# Power_SwitchRegulators.net
KiCad netlist of a schematic drawn in Altium Designer
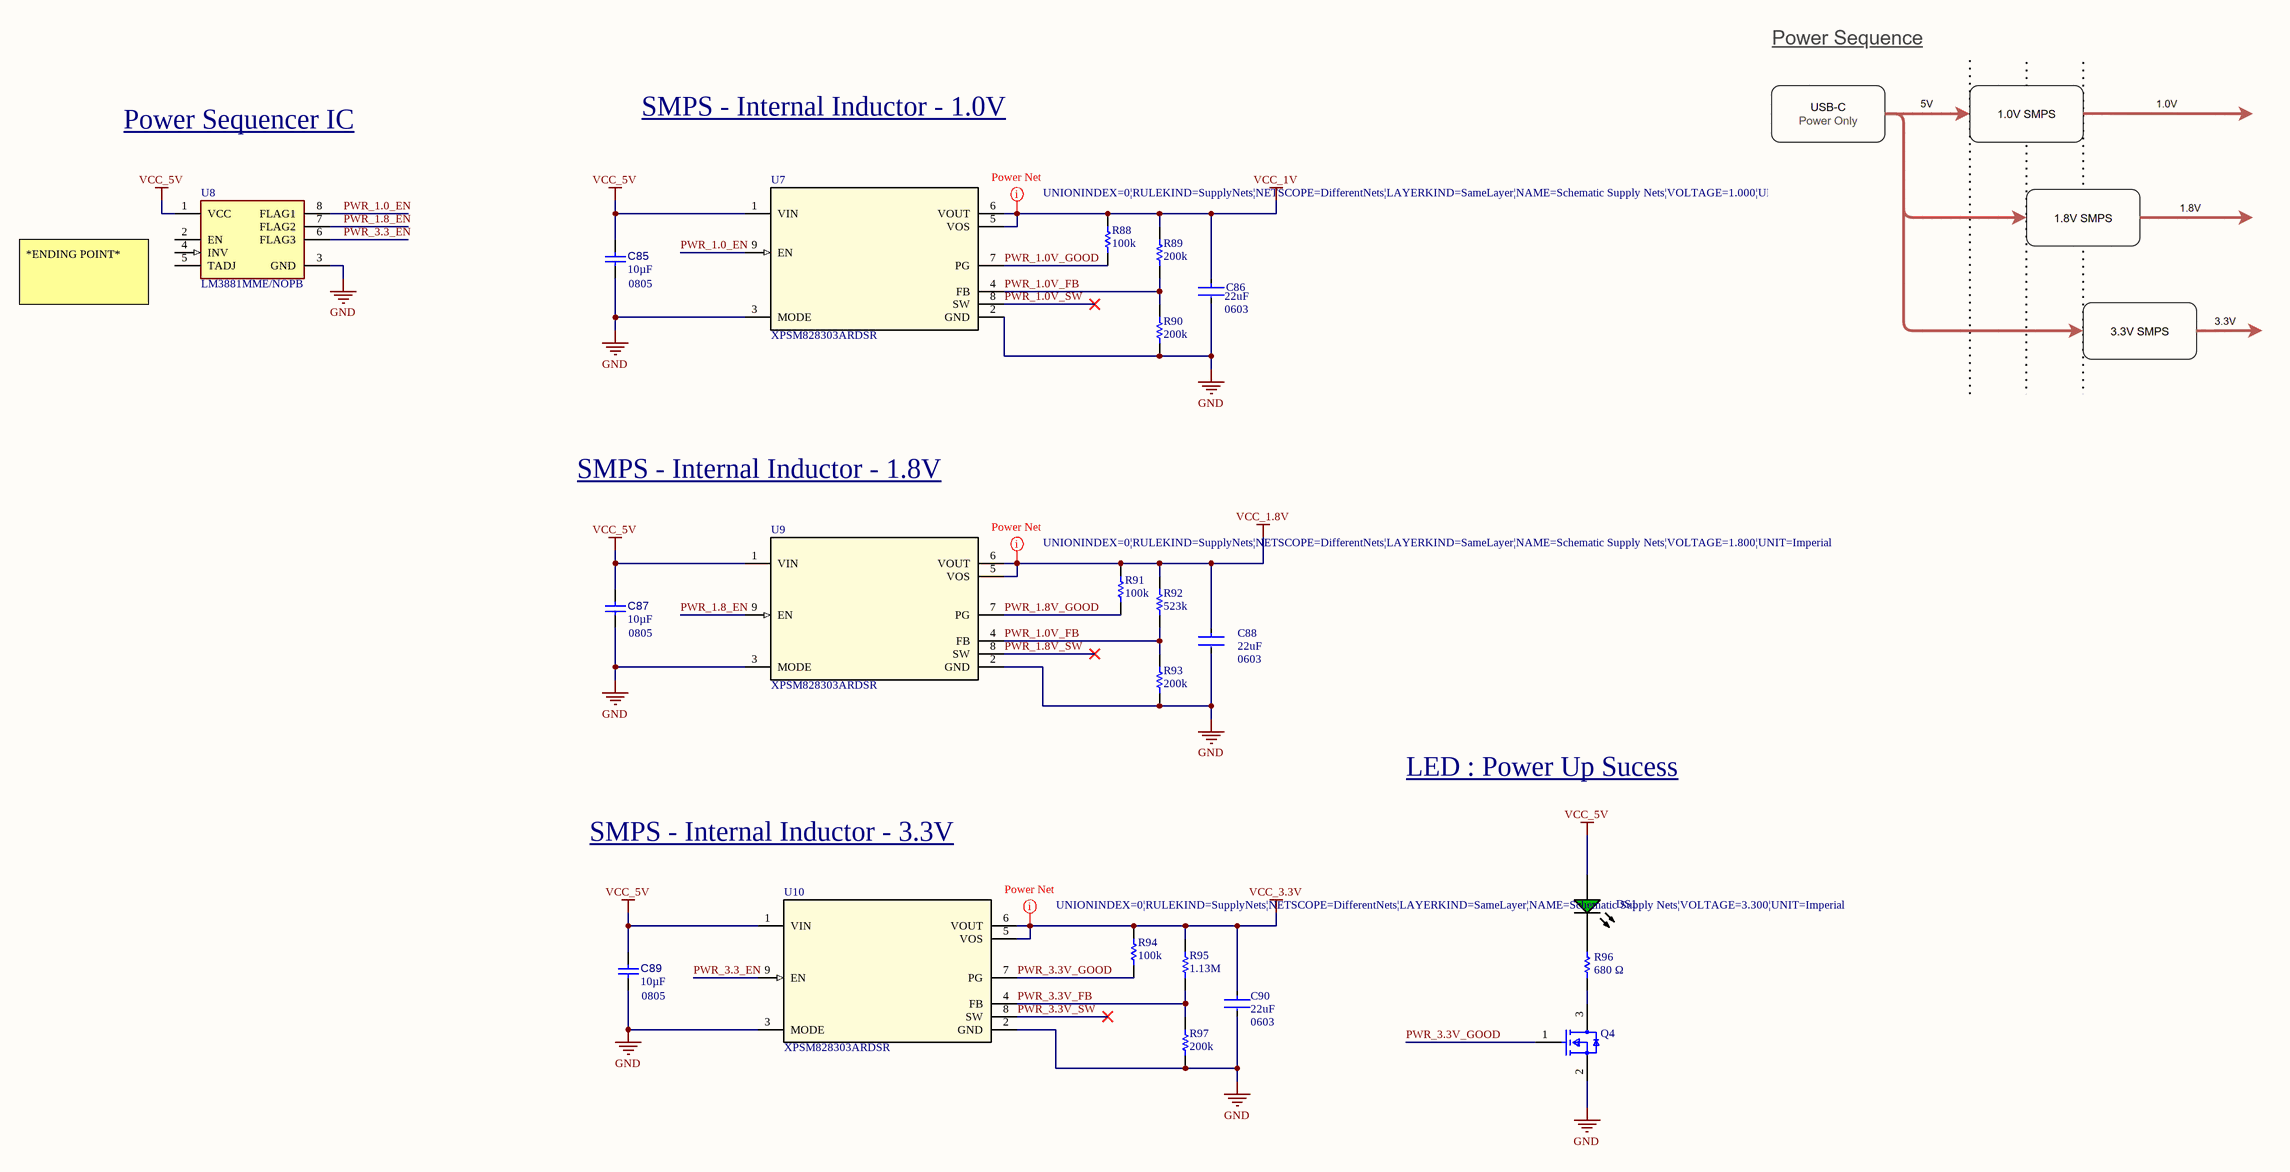
[diagram p0: Power_SwitchRegulators.SchDoc]

(export (version "E")
  (design (tool "Eeschema 10.0.6"))
  (components
    (comp (ref "C85")
      (value "10µF")
      (footprint "CAPC0805(2012)145_L")
      (description "Chip Capacitor, 10µF +/-20%, 25V, 0805, Thickness 1.45 mm")
      (fields
        (field (name "TOLERANCE") "10%")
        (field (name "CASE/PACKAGE") "0805")
        (field (name "Comment") "Capacitor 10µF +/-20% 25V 0805")
      )
      (libsource (lib "Personal Workspace") (part "CAP-NP-2"))
    )
    (comp (ref "C86")
      (value "GRM188R60J226MEA0J")
      (footprint "FP-GRM188-0_2-IPC_C")
      (description "Chip Multilayer Ceramic Capacitors for General Purpose, 0603, 22uF, X5R, 15%, 20%, 6.3V")
      (fields
        (field (name "CAPACITANCE") "22uF")
        (field (name "TOLERANCE") "20%")
        (field (name "CASE/PACKAGE") "0603")
      )
      (libsource (lib "Altium Content Vault") (part "11868f565c42a9108669ba33697ecf6"))
    )
    (comp (ref "C87")
      (value "10µF")
      (footprint "CAPC0805(2012)145_L")
      (description "Chip Capacitor, 10µF +/-20%, 25V, 0805, Thickness 1.45 mm")
      (fields
        (field (name "TOLERANCE") "10%")
        (field (name "CASE/PACKAGE") "0805")
        (field (name "Comment") "Capacitor 10µF +/-20% 25V 0805")
      )
      (libsource (lib "Personal Workspace") (part "CAP-NP-2"))
    )
    (comp (ref "C88")
      (value "GRM188R60J226MEA0J")
      (footprint "FP-GRM188-0_2-IPC_C")
      (description "Chip Multilayer Ceramic Capacitors for General Purpose, 0603, 22uF, X5R, 15%, 20%, 6.3V")
      (fields
        (field (name "CAPACITANCE") "22uF")
        (field (name "TOLERANCE") "20%")
        (field (name "CASE/PACKAGE") "0603")
      )
      (libsource (lib "Altium Content Vault") (part "11868f565c42a9108669ba33697ecf6"))
    )
    (comp (ref "C89")
      (value "10µF")
      (footprint "CAPC0805(2012)145_L")
      (description "Chip Capacitor, 10µF +/-20%, 25V, 0805, Thickness 1.45 mm")
      (fields
        (field (name "TOLERANCE") "10%")
        (field (name "CASE/PACKAGE") "0805")
        (field (name "Comment") "Capacitor 10µF +/-20% 25V 0805")
      )
      (libsource (lib "Personal Workspace") (part "CAP-NP-2"))
    )
    (comp (ref "C90")
      (value "GRM188R60J226MEA0J")
      (footprint "FP-GRM188-0_2-IPC_C")
      (description "Chip Multilayer Ceramic Capacitors for General Purpose, 0603, 22uF, X5R, 15%, 20%, 6.3V")
      (fields
        (field (name "CAPACITANCE") "22uF")
        (field (name "TOLERANCE") "20%")
        (field (name "CASE/PACKAGE") "0603")
      )
      (libsource (lib "Altium Content Vault") (part "11868f565c42a9108669ba33697ecf6"))
    )
    (comp (ref "DS1")
      (value "HSMG-C170")
      (footprint "AVAG-HSMX-C170_V")
      (description "Chip LED, Green, 2.2 V, -40 to 85 degC, 2-Pin SMD, Pb-Free, Tape and Reel")
      (fields (field (name "MANUFACTURER") "Avago"))
      (libsource (lib "Altium Content Vault") (part "LED_GREEN_A1K2-2"))
    )
    (comp (ref "Q4")
      (value "BSS138")
      (footprint "FP-318-08-IPC_B")
      (description "MOSFET N-CH 50V 220MA SOT-23")
      (libsource (lib "Altium Content Vault") (part "3b9c635fedb024a5347a57b145af9cc"))
    )
    (comp (ref "R88")
      (value "100k")
      (footprint "RESC1005X40X25ML05T05")
      (description "Chip Resistor, 100 KOhm, +/- 1%, 0.063 W, -55 to 155 degC, 0402 (1005 Metric)")
      (fields (field (name "POWER") "63mW") (field (name "TOLERANCE") "1%"))
      (libsource (lib "Personal Workspace") (part "RES-2"))
    )
    (comp (ref "R89")
      (value "200k")
      (footprint "RESC0402(1005)_L")
      (description "Chip Resistor, 200 kOhms, +/-1 %, 63 mW, -55 to 155 degC, 0402")
      (fields (field (name "TOLERANCE") "1%") (field (name "POWER") "63mW"))
      (libsource (lib "Personal Workspace") (part "RES-2"))
    )
    (comp (ref "R90")
      (value "200k")
      (footprint "RESC0402(1005)_L")
      (description "Chip Resistor, 200 kOhms, +/-1 %, 63 mW, -55 to 155 degC, 0402")
      (fields (field (name "TOLERANCE") "1%") (field (name "POWER") "63mW"))
      (libsource (lib "Personal Workspace") (part "RES-2"))
    )
    (comp (ref "R91")
      (value "100k")
      (footprint "RESC1005X40X25ML05T05")
      (description "Chip Resistor, 100 KOhm, +/- 1%, 0.063 W, -55 to 155 degC, 0402 (1005 Metric)")
      (fields (field (name "POWER") "63mW") (field (name "TOLERANCE") "1%"))
      (libsource (lib "Personal Workspace") (part "RES-2"))
    )
    (comp (ref "R92")
      (value "523k")
      (footprint "RESC1005X40X25LL10T10")
      (description "Res Thick Film 0402 523K Ohm 1% 1/16W 100ppm/C Molded SMD SMD Paper Tape on Plastic Reel")
      (fields (field (name "TOLERANCE") "1%") (field (name "Comment") "CR0402-FX-5233GLF"))
      (libsource (lib "Personal Workspace") (part "RES"))
    )
    (comp (ref "R93")
      (value "200k")
      (footprint "RESC0402(1005)_L")
      (description "Chip Resistor, 200 kOhms, +/-1 %, 63 mW, -55 to 155 degC, 0402")
      (fields (field (name "TOLERANCE") "1%") (field (name "POWER") "63mW"))
      (libsource (lib "Personal Workspace") (part "RES-2"))
    )
    (comp (ref "R94")
      (value "100k")
      (footprint "RESC1005X40X25ML05T05")
      (description "Chip Resistor, 100 KOhm, +/- 1%, 0.063 W, -55 to 155 degC, 0402 (1005 Metric)")
      (fields (field (name "POWER") "63mW") (field (name "TOLERANCE") "1%"))
      (libsource (lib "Personal Workspace") (part "RES-2"))
    )
    (comp (ref "R95")
      (value "1.13M")
      (footprint "RESC1005X40X25NL05T05")
      (description "Res Thick Film 0402 1.13M Ohm 1% 0.063W(1/16W) ±100ppm/C Pad SMD T/R Automotive")
      (fields (field (name "TOLERANCE") "1%") (field (name "Comment") "CRCW04021M13FKED"))
      (libsource (lib "Personal Workspace") (part "RES-2"))
    )
    (comp (ref "R96")
      (value "RC0603JR-070RL")
      (footprint "RESC1608X55X25ML10T15")
      (description "Chip Resistor, 0 Ohm, +/- 5%, 0.1 W, -55 to 155 degC, 0603 (1608 Metric), RoHS, Tape and Reel")
      (fields
        (field (name "TOLERANCE") "5%")
        (field (name "RESISTANCE") "680 Ω")
        (field (name "MANUFACTURER") "Yageo")
      )
      (libsource (lib "Altium Content Vault") (part "RES-2"))
    )
    (comp (ref "R97")
      (value "200k")
      (footprint "RESC0402(1005)_L")
      (description "Chip Resistor, 200 kOhms, +/-1 %, 63 mW, -55 to 155 degC, 0402")
      (fields (field (name "TOLERANCE") "1%") (field (name "POWER") "63mW"))
      (libsource (lib "Personal Workspace") (part "RES-2"))
    )
    (comp (ref "U7")
      (value "XPSM828303ARDSR")
      (footprint "RDS0009A-MFG")
      (fields (field (name "COPYRIGHT") "Copyright (C) 2025 Ultra Librarian. All rights reserved."))
      (libsource (lib "Personal Workspace") (part "XPSM828303ARDSR"))
    )
    (comp (ref "U8")
      (value "LM3881MME/NOPB")
      (footprint "FP-DGK0008A-IPC_B")
      (description "3 rail simple power sequencer with adjustable time delay 8-VSSOP -40 to 125")
      (libsource (lib "Personal Workspace") (part "8217977d3e9fd648f3782d3b262e5ea"))
    )
    (comp (ref "U9")
      (value "XPSM828303ARDSR")
      (footprint "RDS0009A-MFG")
      (fields (field (name "COPYRIGHT") "Copyright (C) 2025 Ultra Librarian. All rights reserved."))
      (libsource (lib "") (part "XPSM828303ARDSR_1"))
    )
    (comp (ref "U10")
      (value "XPSM828303ARDSR")
      (footprint "RDS0009A-MFG")
      (fields (field (name "COPYRIGHT") "Copyright (C) 2025 Ultra Librarian. All rights reserved."))
      (libsource (lib "") (part "XPSM828303ARDSR_1"))
    )
  )
  (nets
    (net (code "1") (name "/PWR_1.0V_FB") (class "Default")
      (node (ref "R89") (pin "1") (pinfunction "1_1") (pintype "passive"))
      (node (ref "R90") (pin "2") (pinfunction "2_2") (pintype "passive"))
      (node (ref "R92") (pin "2") (pinfunction "2_2") (pintype "passive"))
      (node (ref "R93") (pin "2") (pinfunction "2_2") (pintype "passive"))
      (node (ref "U7") (pin "4") (pinfunction "FB_4") (pintype "passive"))
      (node (ref "U9") (pin "4") (pinfunction "FB_4") (pintype "passive"))
    )
    (net (code "2") (name "/PWR_1.0V_GOOD") (class "Default")
      (node (ref "R88") (pin "1") (pinfunction "1_1") (pintype "passive"))
      (node (ref "U7") (pin "7") (pinfunction "PG_7") (pintype "open_collector"))
    )
    (net (code "3") (name "/PWR_1.0V_SW") (class "Default")
      (node (ref "U7") (pin "8") (pinfunction "SW_8") (pintype "passive+no_connect"))
    )
    (net (code "4") (name "/PWR_1.0_EN") (class "Default")
      (node (ref "U7") (pin "9") (pinfunction "EN_9") (pintype "input"))
      (node (ref "U8") (pin "8") (pinfunction "FLAG1_8") (pintype "open_collector"))
    )
    (net (code "5") (name "/PWR_1.8V_GOOD") (class "Default")
      (node (ref "R91") (pin "1") (pinfunction "1_1") (pintype "passive"))
      (node (ref "U9") (pin "7") (pinfunction "PG_7") (pintype "open_collector"))
    )
    (net (code "6") (name "/PWR_1.8V_SW") (class "Default")
      (node (ref "U9") (pin "8") (pinfunction "SW_8") (pintype "passive+no_connect"))
    )
    (net (code "7") (name "/PWR_1.8_EN") (class "Default")
      (node (ref "U8") (pin "7") (pinfunction "FLAG2_7") (pintype "open_collector"))
      (node (ref "U9") (pin "9") (pinfunction "EN_9") (pintype "input"))
    )
    (net (code "8") (name "/PWR_3.3V_FB") (class "Default")
      (node (ref "R95") (pin "1") (pinfunction "1_1") (pintype "passive"))
      (node (ref "R97") (pin "2") (pinfunction "2_2") (pintype "passive"))
      (node (ref "U10") (pin "4") (pinfunction "FB_4") (pintype "passive"))
    )
    (net (code "9") (name "/PWR_3.3V_GOOD") (class "Default")
      (node (ref "Q4") (pin "1") (pinfunction "G_1") (pintype "passive"))
      (node (ref "R94") (pin "1") (pinfunction "1_1") (pintype "passive"))
      (node (ref "U10") (pin "7") (pinfunction "PG_7") (pintype "open_collector"))
    )
    (net (code "10") (name "/PWR_3.3V_SW") (class "Default")
      (node (ref "U10") (pin "8") (pinfunction "SW_8") (pintype "passive+no_connect"))
    )
    (net (code "11") (name "/PWR_3.3_EN") (class "Default")
      (node (ref "U10") (pin "9") (pinfunction "EN_9") (pintype "input"))
      (node (ref "U8") (pin "6") (pinfunction "FLAG3_6") (pintype "open_collector"))
    )
    (net (code "12") (name "GND") (class "Default")
      (node (ref "C85") (pin "1") (pinfunction "1_1") (pintype "passive"))
      (node (ref "C86") (pin "2") (pinfunction "2_2") (pintype "passive"))
      (node (ref "C87") (pin "1") (pinfunction "1_1") (pintype "passive"))
      (node (ref "C88") (pin "2") (pinfunction "2_2") (pintype "passive"))
      (node (ref "C89") (pin "1") (pinfunction "1_1") (pintype "passive"))
      (node (ref "C90") (pin "2") (pinfunction "2_2") (pintype "passive"))
      (node (ref "Q4") (pin "2") (pinfunction "S_2") (pintype "passive"))
      (node (ref "R90") (pin "1") (pinfunction "1_1") (pintype "passive"))
      (node (ref "R93") (pin "1") (pinfunction "1_1") (pintype "passive"))
      (node (ref "R97") (pin "1") (pinfunction "1_1") (pintype "passive"))
      (node (ref "U10") (pin "2") (pinfunction "GND_2") (pintype "power_in"))
      (node (ref "U10") (pin "3") (pinfunction "MODE_3") (pintype "passive"))
      (node (ref "U7") (pin "2") (pinfunction "GND_2") (pintype "power_in"))
      (node (ref "U7") (pin "3") (pinfunction "MODE_3") (pintype "passive"))
      (node (ref "U8") (pin "3") (pinfunction "GND_3") (pintype "power_in"))
      (node (ref "U9") (pin "2") (pinfunction "GND_2") (pintype "power_in"))
      (node (ref "U9") (pin "3") (pinfunction "MODE_3") (pintype "passive"))
    )
    (net (code "13") (name "Net-(DS1-K)") (class "Default")
      (node (ref "DS1") (pin "2") (pinfunction "K_2") (pintype "passive"))
      (node (ref "R96") (pin "1") (pinfunction "1_1") (pintype "passive"))
    )
    (net (code "14") (name "Net-(Q4-D)") (class "Default")
      (node (ref "Q4") (pin "3") (pinfunction "D_3") (pintype "passive"))
      (node (ref "R96") (pin "2") (pinfunction "2_2") (pintype "passive"))
    )
    (net (code "15") (name "VCC_1.8V") (class "Default")
      (node (ref "C88") (pin "1") (pinfunction "1_1") (pintype "passive"))
      (node (ref "R91") (pin "2") (pinfunction "2_2") (pintype "passive"))
      (node (ref "R92") (pin "1") (pinfunction "1_1") (pintype "passive"))
      (node (ref "U9") (pin "5") (pinfunction "VOS_5") (pintype "passive"))
      (node (ref "U9") (pin "6") (pinfunction "VOUT_6") (pintype "power_in"))
    )
    (net (code "16") (name "VCC_1V") (class "Default")
      (node (ref "C86") (pin "1") (pinfunction "1_1") (pintype "passive"))
      (node (ref "R88") (pin "2") (pinfunction "2_2") (pintype "passive"))
      (node (ref "R89") (pin "2") (pinfunction "2_2") (pintype "passive"))
      (node (ref "U7") (pin "5") (pinfunction "VOS_5") (pintype "passive"))
      (node (ref "U7") (pin "6") (pinfunction "VOUT_6") (pintype "power_in"))
    )
    (net (code "17") (name "VCC_3.3V") (class "Default")
      (node (ref "C90") (pin "1") (pinfunction "1_1") (pintype "passive"))
      (node (ref "R94") (pin "2") (pinfunction "2_2") (pintype "passive"))
      (node (ref "R95") (pin "2") (pinfunction "2_2") (pintype "passive"))
      (node (ref "U10") (pin "5") (pinfunction "VOS_5") (pintype "passive"))
      (node (ref "U10") (pin "6") (pinfunction "VOUT_6") (pintype "power_in"))
    )
    (net (code "18") (name "VCC_5V") (class "Default")
      (node (ref "C85") (pin "2") (pinfunction "2_2") (pintype "passive"))
      (node (ref "C87") (pin "2") (pinfunction "2_2") (pintype "passive"))
      (node (ref "C89") (pin "2") (pinfunction "2_2") (pintype "passive"))
      (node (ref "DS1") (pin "1") (pinfunction "A_1") (pintype "passive"))
      (node (ref "U10") (pin "1") (pinfunction "VIN_1") (pintype "power_in"))
      (node (ref "U7") (pin "1") (pinfunction "VIN_1") (pintype "power_in"))
      (node (ref "U8") (pin "1") (pinfunction "VCC_1") (pintype "power_in"))
      (node (ref "U9") (pin "1") (pinfunction "VIN_1") (pintype "power_in"))
    )
    (net (code "19") (name "unconnected-(U8-EN-Pad2)") (class "Default")
      (node (ref "U8") (pin "2") (pinfunction "EN_2") (pintype "passive"))
    )
    (net (code "20") (name "unconnected-(U8-INV-Pad4)") (class "Default")
      (node (ref "U8") (pin "4") (pinfunction "INV_4") (pintype "input"))
    )
    (net (code "21") (name "unconnected-(U8-TADJ-Pad5)") (class "Default")
      (node (ref "U8") (pin "5") (pinfunction "TADJ_5") (pintype "passive"))
    )
  )
)
